# Metlino_CLK_Distribution.net
KiCad netlist of a schematic drawn in Altium Designer
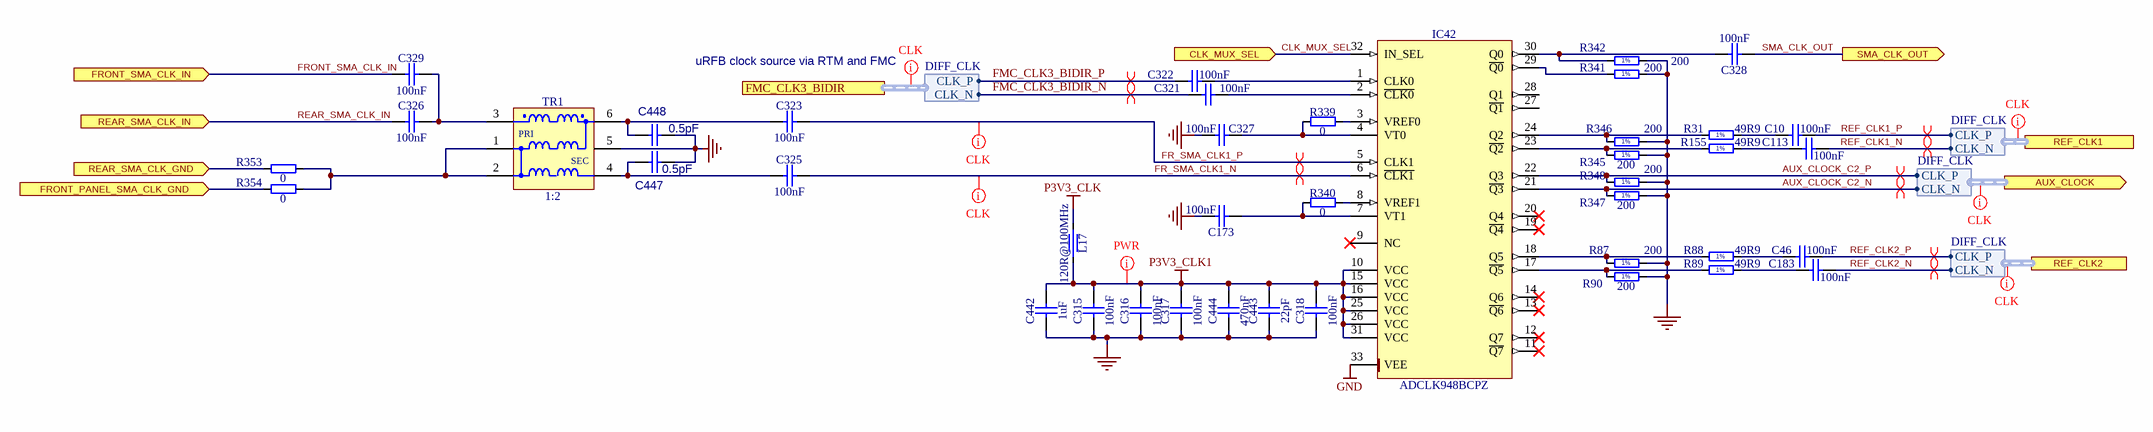
[diagram p0: Metlino_CLK_Distribution.SchDoc]

(export (version "E")
  (design (tool "Eeschema 10.0.6"))
  (components
    (comp (ref "C10")
      (value "100nF")
      (footprint "CAPC0603X33N")
      (description "Non-polarised capacitor")
      (fields
        (field (name "MANUFACTURER PART NUMBER") "CC0201_100NF_6.3V_10%_X5R")
        (field (name "MANUFACTURER") "GENERIC")
        (field (name "AUTHOR") "CERN DEM JLC")
      )
      (libsource (lib "Capacitors") (part "Capacitor - non polarized"))
    )
    (comp (ref "C46")
      (value "100nF")
      (footprint "CAPC0603X33N")
      (description "Non-polarised capacitor")
      (fields
        (field (name "MANUFACTURER PART NUMBER") "CC0201_100NF_6.3V_10%_X5R")
        (field (name "MANUFACTURER") "GENERIC")
        (field (name "AUTHOR") "CERN DEM JLC")
      )
      (libsource (lib "Capacitors") (part "Capacitor - non polarized"))
    )
    (comp (ref "C113")
      (value "100nF")
      (footprint "CAPC0603X33N")
      (description "Non-polarised capacitor")
      (fields
        (field (name "MANUFACTURER PART NUMBER") "CC0201_100NF_6.3V_10%_X5R")
        (field (name "MANUFACTURER") "GENERIC")
        (field (name "AUTHOR") "CERN DEM JLC")
      )
      (libsource (lib "Capacitors") (part "Capacitor - non polarized"))
    )
    (comp (ref "C173")
      (value "100nF")
      (footprint "CAPC0603X33N")
      (description "Non-polarised capacitor")
      (fields
        (field (name "MANUFACTURER PART NUMBER") "CC0201_100NF_6.3V_10%_X5R")
        (field (name "MANUFACTURER") "GENERIC")
        (field (name "AUTHOR") "CERN DEM JLC")
      )
      (libsource (lib "Capacitors") (part "Capacitor - non polarized"))
    )
    (comp (ref "C183")
      (value "100nF")
      (footprint "CAPC0603X33N")
      (description "Non-polarised capacitor")
      (fields
        (field (name "MANUFACTURER PART NUMBER") "CC0201_100NF_6.3V_10%_X5R")
        (field (name "MANUFACTURER") "GENERIC")
        (field (name "AUTHOR") "CERN DEM JLC")
      )
      (libsource (lib "Capacitors") (part "Capacitor - non polarized"))
    )
    (comp (ref "C315")
      (value "100nF")
      (footprint "CAPC0603X33N")
      (description "Non-polarised capacitor")
      (fields
        (field (name "MANUFACTURER PART NUMBER") "CC0201_100NF_6.3V_10%_X5R")
        (field (name "MANUFACTURER") "GENERIC")
        (field (name "AUTHOR") "CERN DEM JLC")
      )
      (libsource (lib "Capacitors") (part "Capacitor - non polarized"))
    )
    (comp (ref "C316")
      (value "100nF")
      (footprint "CAPC0603X33N")
      (description "Non-polarised capacitor")
      (fields
        (field (name "MANUFACTURER PART NUMBER") "CC0201_100NF_6.3V_10%_X5R")
        (field (name "MANUFACTURER") "GENERIC")
        (field (name "AUTHOR") "CERN DEM JLC")
      )
      (libsource (lib "Capacitors") (part "Capacitor - non polarized"))
    )
    (comp (ref "C317")
      (value "100nF")
      (footprint "CAPC0603X33N")
      (description "Non-polarised capacitor")
      (fields
        (field (name "MANUFACTURER PART NUMBER") "CC0201_100NF_6.3V_10%_X5R")
        (field (name "MANUFACTURER") "GENERIC")
        (field (name "AUTHOR") "CERN DEM JLC")
      )
      (libsource (lib "Capacitors") (part "Capacitor - non polarized"))
    )
    (comp (ref "C318")
      (value "100nF")
      (footprint "CAPC0603X33N")
      (description "Non-polarised capacitor")
      (fields
        (field (name "MANUFACTURER PART NUMBER") "CC0201_100NF_6.3V_10%_X5R")
        (field (name "MANUFACTURER") "GENERIC")
        (field (name "AUTHOR") "CERN DEM JLC")
      )
      (libsource (lib "Capacitors") (part "Capacitor - non polarized"))
    )
    (comp (ref "C321")
      (value "100nF")
      (footprint "CAPC0603X33N")
      (description "Non-polarised capacitor")
      (fields
        (field (name "MANUFACTURER PART NUMBER") "CC0201_100NF_6.3V_10%_X5R")
        (field (name "MANUFACTURER") "GENERIC")
        (field (name "AUTHOR") "CERN DEM JLC")
      )
      (libsource (lib "Capacitors") (part "Capacitor - non polarized"))
    )
    (comp (ref "C322")
      (value "100nF")
      (footprint "CAPC0603X33N")
      (description "Non-polarised capacitor")
      (fields
        (field (name "MANUFACTURER PART NUMBER") "CC0201_100NF_6.3V_10%_X5R")
        (field (name "MANUFACTURER") "GENERIC")
        (field (name "AUTHOR") "CERN DEM JLC")
      )
      (libsource (lib "Capacitors") (part "Capacitor - non polarized"))
    )
    (comp (ref "C323")
      (value "100nF")
      (footprint "CAPC0603X33N")
      (description "Non-polarised capacitor")
      (fields
        (field (name "MANUFACTURER PART NUMBER") "CC0201_100NF_6.3V_10%_X5R")
        (field (name "MANUFACTURER") "GENERIC")
        (field (name "AUTHOR") "CERN DEM JLC")
      )
      (libsource (lib "Capacitors") (part "Capacitor - non polarized"))
    )
    (comp (ref "C325")
      (value "100nF")
      (footprint "CAPC0603X33N")
      (description "Non-polarised capacitor")
      (fields
        (field (name "MANUFACTURER PART NUMBER") "CC0201_100NF_6.3V_10%_X5R")
        (field (name "MANUFACTURER") "GENERIC")
        (field (name "AUTHOR") "CERN DEM JLC")
      )
      (libsource (lib "Capacitors") (part "Capacitor - non polarized"))
    )
    (comp (ref "C326")
      (value "100nF")
      (footprint "CAPC0603X33N")
      (description "Non-polarised capacitor")
      (fields
        (field (name "MANUFACTURER PART NUMBER") "CC0201_100NF_6.3V_10%_X5R")
        (field (name "MANUFACTURER") "GENERIC")
        (field (name "AUTHOR") "CERN DEM JLC")
      )
      (libsource (lib "Capacitors") (part "Capacitor - non polarized"))
    )
    (comp (ref "C327")
      (value "100nF")
      (footprint "CAPC0603X33N")
      (description "Non-polarised capacitor")
      (fields
        (field (name "MANUFACTURER PART NUMBER") "CC0201_100NF_6.3V_10%_X5R")
        (field (name "MANUFACTURER") "GENERIC")
        (field (name "AUTHOR") "CERN DEM JLC")
      )
      (libsource (lib "Capacitors") (part "Capacitor - non polarized"))
    )
    (comp (ref "C328")
      (value "100nF")
      (footprint "CAPC0603X33N")
      (description "Non-polarised capacitor")
      (fields
        (field (name "MANUFACTURER PART NUMBER") "CC0201_100NF_6.3V_10%_X5R")
        (field (name "MANUFACTURER") "GENERIC")
        (field (name "AUTHOR") "CERN DEM JLC")
      )
      (libsource (lib "Capacitors") (part "Capacitor - non polarized"))
    )
    (comp (ref "C329")
      (value "100nF")
      (footprint "CAPC0603X33N")
      (description "Non-polarised capacitor")
      (fields
        (field (name "MANUFACTURER PART NUMBER") "CC0201_100NF_6.3V_10%_X5R")
        (field (name "MANUFACTURER") "GENERIC")
        (field (name "AUTHOR") "CERN DEM JLC")
      )
      (libsource (lib "Capacitors") (part "Capacitor - non polarized"))
    )
    (comp (ref "C442")
      (value "1uF")
      (footprint "CAPC1005X55N")
      (description "Non-polarised capacitor")
      (fields
        (field (name "MANUFACTURER PART NUMBER") "CC0402_1UF_16V_10%_X5R")
        (field (name "MANUFACTURER") "GENERIC")
        (field (name "AUTHOR") "CERN DEM JLC")
      )
      (libsource (lib "Capacitors") (part "Capacitor - non polarized"))
    )
    (comp (ref "C443")
      (value "22pF")
      (footprint "CAPC1005X55N")
      (description "Non-polarised capacitor")
      (fields
        (field (name "MANUFACTURER PART NUMBER") "CC0402_22PF_50V_5%_C0G")
        (field (name "MANUFACTURER") "GENERIC")
        (field (name "AUTHOR") "CERN DEM JLC")
      )
      (libsource (lib "Capacitors") (part "Capacitor - non polarized"))
    )
    (comp (ref "C444")
      (value "470nF")
      (footprint "CAPC1005X55N")
      (description "Non-polarised capacitor")
      (fields
        (field (name "MANUFACTURER PART NUMBER") "CC0402_470NF_16V_10%_X5R")
        (field (name "MANUFACTURER") "GENERIC")
        (field (name "AUTHOR") "CERN DEM JLC")
      )
      (libsource (lib "Capacitors") (part "Capacitor - non polarized"))
    )
    (comp (ref "C447")
      (value "0.5pF")
      (footprint "CAPC1005X55N")
      (fields
        (field (name "$$NOTCOMMONPROPERTY_GENERAL PART NUMBER") "CC0402_0.5PF_25V_0.25PF_C0G")
        (field (name "$$NOTCOMMONPROPERTY_MANUFACTURER1 PART NUMBER") "04023J0R5ABSTR")
        (field (name "MANUFACTURER PART NUMBER") "CC0402_0.5PF_25V_0.05PF_C0G")
      )
      (libsource (lib "altium-import") (part "root_0__*"))
    )
    (comp (ref "C448")
      (value "0.5pF")
      (footprint "CAPC1005X55N")
      (fields
        (field (name "$$NOTCOMMONPROPERTY_GENERAL PART NUMBER") "CC0402_0.5PF_25V_0.25PF_C0G")
        (field (name "$$NOTCOMMONPROPERTY_MANUFACTURER1 PART NUMBER") "04023J0R5ABSTR")
        (field (name "MANUFACTURER PART NUMBER") "CC0402_0.5PF_25V_0.05PF_C0G")
      )
      (libsource (lib "altium-import") (part "root_0__*"))
    )
    (comp (ref "IC42")
      (value "ADCLK948BCPZ")
      (footprint "QFN50P500X500X80-33N-S285")
      (description "Two Selectable Inputs, 8 LVPECL Outputs, SiGe Clock Fanout Buffer")
      (fields (field (name "MANUFACTURER") "ANALOG DEVICES") (field (name "AUTHOR") "CERN DEM MR"))
      (libsource (lib "ICs And Semiconductors") (part "ADCLK948"))
    )
    (comp (ref "L17")
      (value "120R@100MHz")
      (footprint "INDC1608X95N")
      (fields
        (field (name "MANUFACTURER PART NUMBER") "BLM18PG121SN1D")
        (field (name "MANUFACTURER") "MURATA")
        (field (name "PART NUMBER") "IND0603_MURATA_BLM18PG121SN1D")
        (field (name "AUTHOR") "CERN DEM BC")
      )
      (libsource (lib "Inductors & Transformers") (part "Ferrite Bead"))
    )
    (comp (ref "R31")
      (value "49R9")
      (footprint "RESC1005X40N")
      (description "Resistor - 1%")
      (fields
        (field (name "MANUFACTURER PART NUMBER") "R0402_49R9_1%_0.0625W_100PPM")
        (field (name "MANUFACTURER") "GENERIC")
        (field (name "AUTHOR") "CERN DEM JLC")
      )
      (libsource (lib "Resistors") (part "Resistor - 1%"))
    )
    (comp (ref "R87")
      (value "200")
      (footprint "RESC1005X40N")
      (description "Resistor - 1%")
      (fields
        (field (name "MANUFACTURER PART NUMBER") "R0402_200R_1%_0.0625W_100PPM")
        (field (name "MANUFACTURER") "GENERIC")
        (field (name "AUTHOR") "CERN DEM JLC")
      )
      (libsource (lib "Resistors") (part "Resistor - 1%"))
    )
    (comp (ref "R88")
      (value "49R9")
      (footprint "RESC1005X40N")
      (description "Resistor - 1%")
      (fields
        (field (name "MANUFACTURER PART NUMBER") "R0402_49R9_1%_0.0625W_100PPM")
        (field (name "MANUFACTURER") "GENERIC")
        (field (name "AUTHOR") "CERN DEM JLC")
      )
      (libsource (lib "Resistors") (part "Resistor - 1%"))
    )
    (comp (ref "R89")
      (value "49R9")
      (footprint "RESC1005X40N")
      (description "Resistor - 1%")
      (fields
        (field (name "MANUFACTURER PART NUMBER") "R0402_49R9_1%_0.0625W_100PPM")
        (field (name "MANUFACTURER") "GENERIC")
        (field (name "AUTHOR") "CERN DEM JLC")
      )
      (libsource (lib "Resistors") (part "Resistor - 1%"))
    )
    (comp (ref "R90")
      (value "200")
      (footprint "RESC1005X40N")
      (description "Resistor - 1%")
      (fields
        (field (name "MANUFACTURER PART NUMBER") "R0402_200R_1%_0.0625W_100PPM")
        (field (name "MANUFACTURER") "GENERIC")
        (field (name "AUTHOR") "CERN DEM JLC")
      )
      (libsource (lib "Resistors") (part "Resistor - 1%"))
    )
    (comp (ref "R155")
      (value "49R9")
      (footprint "RESC1005X40N")
      (description "Resistor - 1%")
      (fields
        (field (name "MANUFACTURER PART NUMBER") "R0402_49R9_1%_0.0625W_100PPM")
        (field (name "MANUFACTURER") "GENERIC")
        (field (name "AUTHOR") "CERN DEM JLC")
      )
      (libsource (lib "Resistors") (part "Resistor - 1%"))
    )
    (comp (ref "R339")
      (value "0")
      (footprint "RESC1005X40N")
      (description "Resistor")
      (fields
        (field (name "MANUFACTURER PART NUMBER") "R0402_0R_JUMPER")
        (field (name "MANUFACTURER") "GENERIC")
        (field (name "AUTHOR") "CERN DEM JLC")
      )
      (libsource (lib "Resistors") (part "Resistor"))
    )
    (comp (ref "R340")
      (value "0")
      (footprint "RESC1005X40N")
      (description "Resistor")
      (fields
        (field (name "MANUFACTURER PART NUMBER") "R0402_0R_JUMPER")
        (field (name "MANUFACTURER") "GENERIC")
        (field (name "AUTHOR") "CERN DEM JLC")
      )
      (libsource (lib "Resistors") (part "Resistor"))
    )
    (comp (ref "R341")
      (value "200")
      (footprint "RESC1005X40N")
      (description "Resistor - 1%")
      (fields
        (field (name "MANUFACTURER PART NUMBER") "R0402_200R_1%_0.0625W_100PPM")
        (field (name "MANUFACTURER") "GENERIC")
        (field (name "AUTHOR") "CERN DEM JLC")
      )
      (libsource (lib "Resistors") (part "Resistor - 1%"))
    )
    (comp (ref "R342")
      (value "200")
      (footprint "RESC1005X40N")
      (description "Resistor - 1%")
      (fields
        (field (name "MANUFACTURER PART NUMBER") "R0402_200R_1%_0.0625W_100PPM")
        (field (name "MANUFACTURER") "GENERIC")
        (field (name "AUTHOR") "CERN DEM JLC")
      )
      (libsource (lib "Resistors") (part "Resistor - 1%"))
    )
    (comp (ref "R345")
      (value "200")
      (footprint "RESC1005X40N")
      (description "Resistor - 1%")
      (fields
        (field (name "MANUFACTURER PART NUMBER") "R0402_200R_1%_0.0625W_100PPM")
        (field (name "MANUFACTURER") "GENERIC")
        (field (name "AUTHOR") "CERN DEM JLC")
      )
      (libsource (lib "Resistors") (part "Resistor - 1%"))
    )
    (comp (ref "R346")
      (value "200")
      (footprint "RESC1005X40N")
      (description "Resistor - 1%")
      (fields
        (field (name "MANUFACTURER PART NUMBER") "R0402_200R_1%_0.0625W_100PPM")
        (field (name "MANUFACTURER") "GENERIC")
        (field (name "AUTHOR") "CERN DEM JLC")
      )
      (libsource (lib "Resistors") (part "Resistor - 1%"))
    )
    (comp (ref "R347")
      (value "200")
      (footprint "RESC1005X40N")
      (description "Resistor - 1%")
      (fields
        (field (name "MANUFACTURER PART NUMBER") "R0402_200R_1%_0.0625W_100PPM")
        (field (name "MANUFACTURER") "GENERIC")
        (field (name "AUTHOR") "CERN DEM JLC")
      )
      (libsource (lib "Resistors") (part "Resistor - 1%"))
    )
    (comp (ref "R348")
      (value "200")
      (footprint "RESC1005X40N")
      (description "Resistor - 1%")
      (fields
        (field (name "MANUFACTURER PART NUMBER") "R0402_200R_1%_0.0625W_100PPM")
        (field (name "MANUFACTURER") "GENERIC")
        (field (name "AUTHOR") "CERN DEM JLC")
      )
      (libsource (lib "Resistors") (part "Resistor - 1%"))
    )
    (comp (ref "R353")
      (value "0")
      (footprint "RESC1005X40N")
      (description "Resistor")
      (fields
        (field (name "MANUFACTURER PART NUMBER") "R0402_0R_JUMPER")
        (field (name "MANUFACTURER") "GENERIC")
        (field (name "AUTHOR") "CERN DEM JLC")
      )
      (libsource (lib "Resistors") (part "Resistor"))
    )
    (comp (ref "R354")
      (value "0")
      (footprint "RESC1005X40N")
      (description "Resistor")
      (fields
        (field (name "MANUFACTURER PART NUMBER") "R0402_0R_JUMPER")
        (field (name "MANUFACTURER") "GENERIC")
        (field (name "AUTHOR") "CERN DEM JLC")
      )
      (libsource (lib "Resistors") (part "Resistor"))
    )
    (comp (ref "TR1")
      (value "1:2")
      (footprint "XFMR_MINI-CIRCUITS_DB1627")
      (description "50 OHMS 10 to 4000 MHz RF Transformer")
      (fields
        (field (name "PART NUMBER") "XFMR_MINI-CIRCUITS_TCM2-43X+")
        (field (name "POWER") "0.4W")
        (field (name "AUTHOR") "CERN DEM BC")
      )
      (libsource (lib "Inductors & Transformers") (part "XFMR_MINI-CIRCUITS_TCM2-43X"))
    )
  )
  (nets
    (net (code "2") (name "/AUX_CLOCK_C2_N") (class "Default")
      (node (ref "IC42") (pin "21") (pinfunction "~{Q3}_21") (pintype "output"))
      (node (ref "R347") (pin "1") (pinfunction "1_1") (pintype "passive"))
    )
    (net (code "3") (name "/AUX_CLOCK_C2_P") (class "Default")
      (node (ref "IC42") (pin "22") (pinfunction "Q3_22") (pintype "output"))
      (node (ref "R348") (pin "1") (pinfunction "1_1") (pintype "passive"))
    )
    (net (code "4") (name "/CLK_MUX_SEL") (class "Default")
      (node (ref "IC42") (pin "32") (pinfunction "IN_SEL_32") (pintype "input"))
    )
    (net (code "5") (name "/FMC_CLK3_BIDIR_N") (class "Default")
      (node (ref "C321") (pin "2") (pinfunction "2_2") (pintype "passive"))
    )
    (net (code "6") (name "/FMC_CLK3_BIDIR_P") (class "Default")
      (node (ref "C322") (pin "2") (pinfunction "2_2") (pintype "passive"))
    )
    (net (code "7") (name "/FRONT_PANEL_SMA_CLK_GND") (class "Default")
      (node (ref "R354") (pin "1") (pinfunction "1_1") (pintype "passive"))
    )
    (net (code "8") (name "/FRONT_SMA_CLK_IN") (class "Default")
      (node (ref "C329") (pin "1") (pinfunction "1_1") (pintype "passive"))
    )
    (net (code "9") (name "/FR_SMA_CLK1_N") (class "Default")
      (node (ref "C325") (pin "2") (pinfunction "2_2") (pintype "passive"))
      (node (ref "IC42") (pin "6") (pinfunction "~{CLK1}_6") (pintype "input"))
    )
    (net (code "10") (name "/FR_SMA_CLK1_P") (class "Default")
      (node (ref "C323") (pin "2") (pinfunction "2_2") (pintype "passive"))
      (node (ref "IC42") (pin "5") (pinfunction "CLK1_5") (pintype "input"))
    )
    (net (code "11") (name "/REAR_SMA_CLK_GND") (class "Default")
      (node (ref "R353") (pin "1") (pinfunction "1_1") (pintype "passive"))
    )
    (net (code "12") (name "/REAR_SMA_CLK_IN") (class "Default")
      (node (ref "C326") (pin "1") (pinfunction "1_1") (pintype "passive"))
    )
    (net (code "13") (name "/REF_CLK1_N") (class "Default")
      (node (ref "C113") (pin "1") (pinfunction "1_1") (pintype "passive"))
    )
    (net (code "14") (name "/REF_CLK1_P") (class "Default")
      (node (ref "C10") (pin "1") (pinfunction "1_1") (pintype "passive"))
    )
    (net (code "15") (name "/REF_CLK2_N") (class "Default")
      (node (ref "C183") (pin "1") (pinfunction "1_1") (pintype "passive"))
    )
    (net (code "16") (name "/REF_CLK2_P") (class "Default")
      (node (ref "C46") (pin "1") (pinfunction "1_1") (pintype "passive"))
    )
    (net (code "17") (name "/SMA_CLK_OUT") (class "Default")
      (node (ref "C328") (pin "1") (pinfunction "1_1") (pintype "passive"))
    )
    (net (code "19") (name "GND") (class "Default")
      (node (ref "C173") (pin "2") (pinfunction "2_2") (pintype "passive"))
      (node (ref "C315") (pin "1") (pinfunction "1_1") (pintype "passive"))
      (node (ref "C316") (pin "1") (pinfunction "1_1") (pintype "passive"))
      (node (ref "C317") (pin "1") (pinfunction "1_1") (pintype "passive"))
      (node (ref "C318") (pin "1") (pinfunction "1_1") (pintype "passive"))
      (node (ref "C327") (pin "2") (pinfunction "2_2") (pintype "passive"))
      (node (ref "C442") (pin "2") (pinfunction "2_2") (pintype "passive"))
      (node (ref "C443") (pin "1") (pinfunction "1_1") (pintype "passive"))
      (node (ref "C444") (pin "1") (pinfunction "1_1") (pintype "passive"))
      (node (ref "C447") (pin "2") (pinfunction "2_2") (pintype "passive"))
      (node (ref "C448") (pin "2") (pinfunction "2_2") (pintype "passive"))
      (node (ref "IC42") (pin "33") (pinfunction "VEE_33") (pintype "power_in"))
      (node (ref "R341") (pin "2") (pinfunction "2_2") (pintype "passive"))
      (node (ref "R342") (pin "2") (pinfunction "2_2") (pintype "passive"))
      (node (ref "R345") (pin "2") (pinfunction "2_2") (pintype "passive"))
      (node (ref "R346") (pin "2") (pinfunction "2_2") (pintype "passive"))
      (node (ref "R347") (pin "2") (pinfunction "2_2") (pintype "passive"))
      (node (ref "R348") (pin "2") (pinfunction "2_2") (pintype "passive"))
      (node (ref "R87") (pin "2") (pinfunction "2_2") (pintype "passive"))
      (node (ref "R90") (pin "2") (pinfunction "2_2") (pintype "passive"))
      (node (ref "TR1") (pin "5") (pinfunction "NC_5") (pintype "passive"))
    )
    (net (code "20") (name "Net-(C10-Pad2)") (class "Default")
      (node (ref "C10") (pin "2") (pinfunction "2_2") (pintype "passive"))
      (node (ref "R31") (pin "2") (pinfunction "2_2") (pintype "passive"))
    )
    (net (code "21") (name "Net-(C46-Pad2)") (class "Default")
      (node (ref "C46") (pin "2") (pinfunction "2_2") (pintype "passive"))
      (node (ref "R88") (pin "2") (pinfunction "2_2") (pintype "passive"))
    )
    (net (code "22") (name "Net-(C113-Pad2)") (class "Default")
      (node (ref "C113") (pin "2") (pinfunction "2_2") (pintype "passive"))
      (node (ref "R155") (pin "2") (pinfunction "2_2") (pintype "passive"))
    )
    (net (code "23") (name "Net-(C183-Pad2)") (class "Default")
      (node (ref "C183") (pin "2") (pinfunction "2_2") (pintype "passive"))
      (node (ref "R89") (pin "2") (pinfunction "2_2") (pintype "passive"))
    )
    (net (code "24") (name "Net-(C323-Pad1)") (class "Default")
      (node (ref "C323") (pin "1") (pinfunction "1_1") (pintype "passive"))
      (node (ref "C448") (pin "1") (pinfunction "1_1") (pintype "passive"))
      (node (ref "TR1") (pin "6") (pinfunction "S1_6") (pintype "passive"))
    )
    (net (code "25") (name "Net-(C325-Pad1)") (class "Default")
      (node (ref "C325") (pin "1") (pinfunction "1_1") (pintype "passive"))
      (node (ref "C447") (pin "1") (pinfunction "1_1") (pintype "passive"))
      (node (ref "TR1") (pin "4") (pinfunction "S1_4") (pintype "passive"))
    )
    (net (code "26") (name "Net-(C326-Pad2)") (class "Default")
      (node (ref "C326") (pin "2") (pinfunction "2_2") (pintype "passive"))
      (node (ref "C329") (pin "2") (pinfunction "2_2") (pintype "passive"))
      (node (ref "TR1") (pin "3") (pinfunction "P1_3") (pintype "passive"))
    )
    (net (code "27") (name "Net-(IC42-CLK0)") (class "Default")
      (node (ref "C322") (pin "1") (pinfunction "1_1") (pintype "passive"))
      (node (ref "IC42") (pin "1") (pinfunction "CLK0_1") (pintype "input"))
    )
    (net (code "28") (name "Net-(IC42-Q0)") (class "Default")
      (node (ref "C328") (pin "2") (pinfunction "2_2") (pintype "passive"))
      (node (ref "IC42") (pin "30") (pinfunction "Q0_30") (pintype "output"))
      (node (ref "R342") (pin "1") (pinfunction "1_1") (pintype "passive"))
    )
    (net (code "29") (name "Net-(IC42-Q2)") (class "Default")
      (node (ref "IC42") (pin "24") (pinfunction "Q2_24") (pintype "output"))
      (node (ref "R31") (pin "1") (pinfunction "1_1") (pintype "passive"))
      (node (ref "R346") (pin "1") (pinfunction "1_1") (pintype "passive"))
    )
    (net (code "30") (name "Net-(IC42-Q5)") (class "Default")
      (node (ref "IC42") (pin "18") (pinfunction "Q5_18") (pintype "output"))
      (node (ref "R87") (pin "1") (pinfunction "1_1") (pintype "passive"))
      (node (ref "R88") (pin "1") (pinfunction "1_1") (pintype "passive"))
    )
    (net (code "31") (name "Net-(IC42-VREF0)") (class "Default")
      (node (ref "IC42") (pin "3") (pinfunction "VREF0_3") (pintype "input"))
      (node (ref "R339") (pin "2") (pinfunction "2_2") (pintype "passive"))
    )
    (net (code "32") (name "Net-(IC42-VREF1)") (class "Default")
      (node (ref "IC42") (pin "8") (pinfunction "VREF1_8") (pintype "input"))
      (node (ref "R340") (pin "2") (pinfunction "2_2") (pintype "passive"))
    )
    (net (code "33") (name "Net-(IC42-VT0)") (class "Default")
      (node (ref "C327") (pin "1") (pinfunction "1_1") (pintype "passive"))
      (node (ref "IC42") (pin "4") (pinfunction "VT0_4") (pintype "passive"))
      (node (ref "R339") (pin "1") (pinfunction "1_1") (pintype "passive"))
    )
    (net (code "34") (name "Net-(IC42-VT1)") (class "Default")
      (node (ref "C173") (pin "1") (pinfunction "1_1") (pintype "passive"))
      (node (ref "IC42") (pin "7") (pinfunction "VT1_7") (pintype "passive"))
      (node (ref "R340") (pin "1") (pinfunction "1_1") (pintype "passive"))
    )
    (net (code "35") (name "Net-(IC42-~{CLK0})") (class "Default")
      (node (ref "C321") (pin "1") (pinfunction "1_1") (pintype "passive"))
      (node (ref "IC42") (pin "2") (pinfunction "~{CLK0}_2") (pintype "input"))
    )
    (net (code "36") (name "Net-(IC42-~{Q0})") (class "Default")
      (node (ref "IC42") (pin "29") (pinfunction "~{Q0}_29") (pintype "output"))
      (node (ref "R341") (pin "1") (pinfunction "1_1") (pintype "passive"))
    )
    (net (code "37") (name "Net-(IC42-~{Q2})") (class "Default")
      (node (ref "IC42") (pin "23") (pinfunction "~{Q2}_23") (pintype "output"))
      (node (ref "R155") (pin "1") (pinfunction "1_1") (pintype "passive"))
      (node (ref "R345") (pin "1") (pinfunction "1_1") (pintype "passive"))
    )
    (net (code "38") (name "Net-(IC42-~{Q5})") (class "Default")
      (node (ref "IC42") (pin "17") (pinfunction "~{Q5}_17") (pintype "output"))
      (node (ref "R89") (pin "1") (pinfunction "1_1") (pintype "passive"))
      (node (ref "R90") (pin "1") (pinfunction "1_1") (pintype "passive"))
    )
    (net (code "39") (name "Net-(R353-Pad2)") (class "Default")
      (node (ref "R353") (pin "2") (pinfunction "2_2") (pintype "passive"))
      (node (ref "R354") (pin "2") (pinfunction "2_2") (pintype "passive"))
      (node (ref "TR1") (pin "1") (pinfunction "P1_1") (pintype "passive"))
      (node (ref "TR1") (pin "2") (pinfunction "P1_2") (pintype "passive"))
    )
    (net (code "40") (name "P3V3_CLK") (class "Default")
      (node (ref "L17") (pin "1") (pinfunction "1_1") (pintype "passive"))
    )
    (net (code "41") (name "P3V3_CLK1") (class "Default")
      (node (ref "C315") (pin "2") (pinfunction "2_2") (pintype "passive"))
      (node (ref "C316") (pin "2") (pinfunction "2_2") (pintype "passive"))
      (node (ref "C317") (pin "2") (pinfunction "2_2") (pintype "passive"))
      (node (ref "C318") (pin "2") (pinfunction "2_2") (pintype "passive"))
      (node (ref "C442") (pin "1") (pinfunction "1_1") (pintype "passive"))
      (node (ref "C443") (pin "2") (pinfunction "2_2") (pintype "passive"))
      (node (ref "C444") (pin "2") (pinfunction "2_2") (pintype "passive"))
      (node (ref "IC42") (pin "10") (pinfunction "VCC_10") (pintype "power_in"))
      (node (ref "IC42") (pin "15") (pinfunction "VCC_15") (pintype "power_in"))
      (node (ref "IC42") (pin "16") (pinfunction "VCC_16") (pintype "power_in"))
      (node (ref "IC42") (pin "25") (pinfunction "VCC_25") (pintype "power_in"))
      (node (ref "IC42") (pin "26") (pinfunction "VCC_26") (pintype "power_in"))
      (node (ref "IC42") (pin "31") (pinfunction "VCC_31") (pintype "power_in"))
      (node (ref "L17") (pin "2") (pinfunction "2_2") (pintype "passive"))
    )
    (net (code "42") (name "unconnected-(IC42-NC-Pad9)") (class "Default")
      (node (ref "IC42") (pin "9") (pinfunction "NC_9") (pintype "passive+no_connect"))
    )
    (net (code "43") (name "unconnected-(IC42-Q1-Pad28)") (class "Default")
      (node (ref "IC42") (pin "28") (pinfunction "Q1_28") (pintype "output"))
    )
    (net (code "44") (name "unconnected-(IC42-Q4-Pad20)") (class "Default")
      (node (ref "IC42") (pin "20") (pinfunction "Q4_20") (pintype "output+no_connect"))
    )
    (net (code "45") (name "unconnected-(IC42-Q6-Pad14)") (class "Default")
      (node (ref "IC42") (pin "14") (pinfunction "Q6_14") (pintype "output+no_connect"))
    )
    (net (code "46") (name "unconnected-(IC42-Q7-Pad12)") (class "Default")
      (node (ref "IC42") (pin "12") (pinfunction "Q7_12") (pintype "output+no_connect"))
    )
    (net (code "47") (name "unconnected-(IC42-~{Q1}-Pad27)") (class "Default")
      (node (ref "IC42") (pin "27") (pinfunction "~{Q1}_27") (pintype "output"))
    )
    (net (code "48") (name "unconnected-(IC42-~{Q4}-Pad19)") (class "Default")
      (node (ref "IC42") (pin "19") (pinfunction "~{Q4}_19") (pintype "output+no_connect"))
    )
    (net (code "49") (name "unconnected-(IC42-~{Q6}-Pad13)") (class "Default")
      (node (ref "IC42") (pin "13") (pinfunction "~{Q6}_13") (pintype "output+no_connect"))
    )
    (net (code "50") (name "unconnected-(IC42-~{Q7}-Pad11)") (class "Default")
      (node (ref "IC42") (pin "11") (pinfunction "~{Q7}_11") (pintype "output+no_connect"))
    )
  )
)
